# register.net
KiCad netlist of a schematic drawn in EAGLE
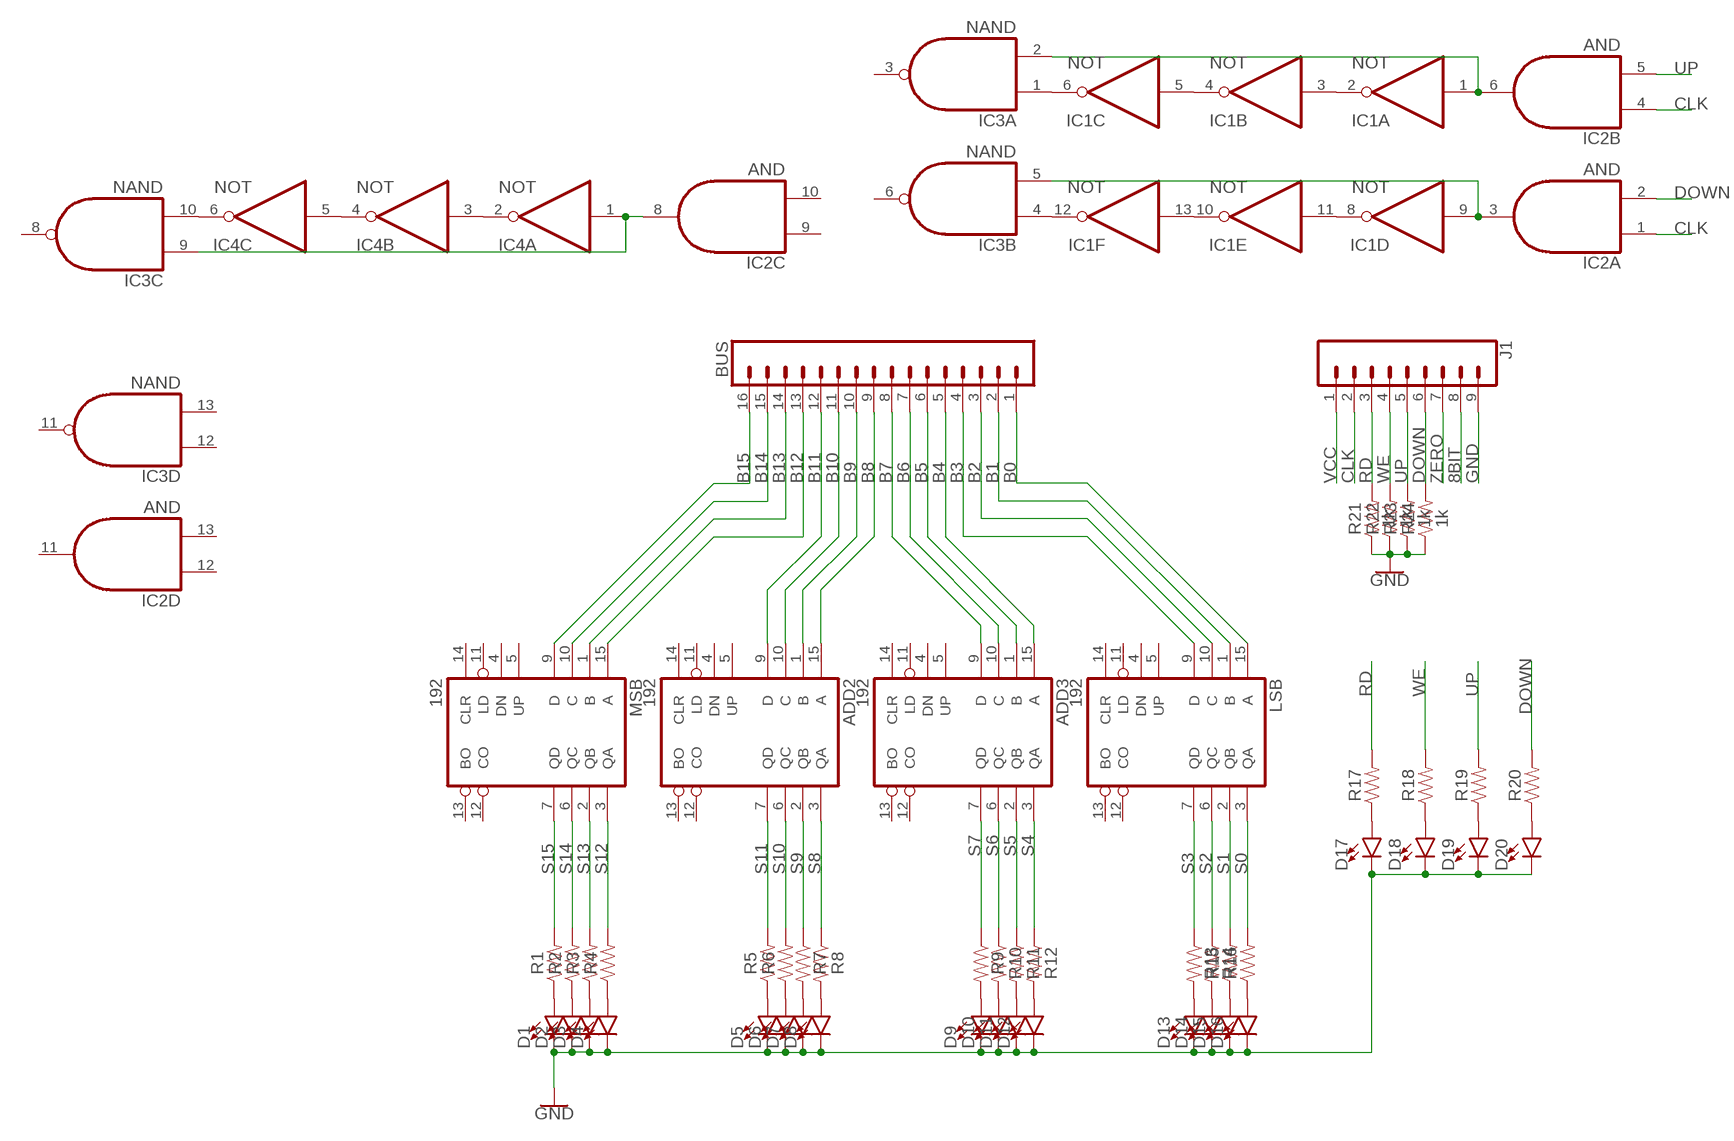
[diagram p0: schematic, sheet 1]

(export (version "E")
  (design (tool "Eeschema 10.0.6"))
  (components
    (comp (ref "ADD2")
      (value "192")
      (footprint "eagle-import:DIL16")
      (libsource (lib "eagle-import") (part "74192NLS"))
    )
    (comp (ref "ADD3")
      (value "192")
      (footprint "eagle-import:DIL16")
      (libsource (lib "eagle-import") (part "74192NLS"))
    )
    (comp (ref "BUS")
      (value "CONN_16")
      (footprint "eagle-import:1X16")
      (libsource (lib "eagle-import") (part "CONN_16"))
    )
    (comp (ref "D1")
      (value "LED5MM")
      (footprint "eagle-import:LED_5MM")
      (libsource (lib "eagle-import") (part "LED5MM"))
    )
    (comp (ref "D2")
      (value "LED5MM")
      (footprint "eagle-import:LED_5MM")
      (libsource (lib "eagle-import") (part "LED5MM"))
    )
    (comp (ref "D3")
      (value "LED5MM")
      (footprint "eagle-import:LED_5MM")
      (libsource (lib "eagle-import") (part "LED5MM"))
    )
    (comp (ref "D4")
      (value "LED5MM")
      (footprint "eagle-import:LED_5MM")
      (libsource (lib "eagle-import") (part "LED5MM"))
    )
    (comp (ref "D5")
      (value "LED5MM")
      (footprint "eagle-import:LED_5MM")
      (libsource (lib "eagle-import") (part "LED5MM"))
    )
    (comp (ref "D6")
      (value "LED5MM")
      (footprint "eagle-import:LED_5MM")
      (libsource (lib "eagle-import") (part "LED5MM"))
    )
    (comp (ref "D7")
      (value "LED5MM")
      (footprint "eagle-import:LED_5MM")
      (libsource (lib "eagle-import") (part "LED5MM"))
    )
    (comp (ref "D8")
      (value "LED5MM")
      (footprint "eagle-import:LED_5MM")
      (libsource (lib "eagle-import") (part "LED5MM"))
    )
    (comp (ref "D9")
      (value "LED5MM")
      (footprint "eagle-import:LED_5MM")
      (libsource (lib "eagle-import") (part "LED5MM"))
    )
    (comp (ref "D10")
      (value "LED5MM")
      (footprint "eagle-import:LED_5MM")
      (libsource (lib "eagle-import") (part "LED5MM"))
    )
    (comp (ref "D11")
      (value "LED5MM")
      (footprint "eagle-import:LED_5MM")
      (libsource (lib "eagle-import") (part "LED5MM"))
    )
    (comp (ref "D12")
      (value "LED5MM")
      (footprint "eagle-import:LED_5MM")
      (libsource (lib "eagle-import") (part "LED5MM"))
    )
    (comp (ref "D13")
      (value "LED5MM")
      (footprint "eagle-import:LED_5MM")
      (libsource (lib "eagle-import") (part "LED5MM"))
    )
    (comp (ref "D14")
      (value "LED5MM")
      (footprint "eagle-import:LED_5MM")
      (libsource (lib "eagle-import") (part "LED5MM"))
    )
    (comp (ref "D15")
      (value "LED5MM")
      (footprint "eagle-import:LED_5MM")
      (libsource (lib "eagle-import") (part "LED5MM"))
    )
    (comp (ref "D16")
      (value "LED5MM")
      (footprint "eagle-import:LED_5MM")
      (libsource (lib "eagle-import") (part "LED5MM"))
    )
    (comp (ref "D17")
      (value "LED5MM")
      (footprint "eagle-import:LED_5MM")
      (libsource (lib "eagle-import") (part "LED5MM"))
    )
    (comp (ref "D18")
      (value "LED5MM")
      (footprint "eagle-import:LED_5MM")
      (libsource (lib "eagle-import") (part "LED5MM"))
    )
    (comp (ref "D19")
      (value "LED5MM")
      (footprint "eagle-import:LED_5MM")
      (libsource (lib "eagle-import") (part "LED5MM"))
    )
    (comp (ref "D20")
      (value "LED5MM")
      (footprint "eagle-import:LED_5MM")
      (libsource (lib "eagle-import") (part "LED5MM"))
    )
    (comp (ref "IC1")
      (value "NOT")
      (footprint "eagle-import:DIL14")
      (libsource (lib "eagle-import") (part "7404NALS"))
    )
    (comp (ref "IC2")
      (value "AND")
      (footprint "eagle-import:DIL14")
      (libsource (lib "eagle-import") (part "7408NALS"))
    )
    (comp (ref "IC3")
      (value "NAND")
      (footprint "eagle-import:DIL14")
      (libsource (lib "eagle-import") (part "7400NALS"))
    )
    (comp (ref "IC4")
      (value "NOT")
      (footprint "eagle-import:DIL14")
      (libsource (lib "eagle-import") (part "7404NALS"))
    )
    (comp (ref "J1")
      (value "CONN_09")
      (footprint "eagle-import:1X09")
      (libsource (lib "eagle-import") (part "CONN_09"))
    )
    (comp (ref "LSB")
      (value "192")
      (footprint "eagle-import:DIL16")
      (libsource (lib "eagle-import") (part "74192NLS"))
    )
    (comp (ref "MSB")
      (value "192")
      (footprint "eagle-import:DIL16")
      (libsource (lib "eagle-import") (part "74192NLS"))
    )
    (comp (ref "R1")
      (value "RESISTORAXIAL-0.3")
      (footprint "eagle-import:AXIAL-0.3")
      (libsource (lib "eagle-import") (part "RESISTORAXIAL-0.3"))
    )
    (comp (ref "R2")
      (value "RESISTORAXIAL-0.3")
      (footprint "eagle-import:AXIAL-0.3")
      (libsource (lib "eagle-import") (part "RESISTORAXIAL-0.3"))
    )
    (comp (ref "R3")
      (value "RESISTORAXIAL-0.3")
      (footprint "eagle-import:AXIAL-0.3")
      (libsource (lib "eagle-import") (part "RESISTORAXIAL-0.3"))
    )
    (comp (ref "R4")
      (value "RESISTORAXIAL-0.3")
      (footprint "eagle-import:AXIAL-0.3")
      (libsource (lib "eagle-import") (part "RESISTORAXIAL-0.3"))
    )
    (comp (ref "R5")
      (value "RESISTORAXIAL-0.3")
      (footprint "eagle-import:AXIAL-0.3")
      (libsource (lib "eagle-import") (part "RESISTORAXIAL-0.3"))
    )
    (comp (ref "R6")
      (value "RESISTORAXIAL-0.3")
      (footprint "eagle-import:AXIAL-0.3")
      (libsource (lib "eagle-import") (part "RESISTORAXIAL-0.3"))
    )
    (comp (ref "R7")
      (value "RESISTORAXIAL-0.3")
      (footprint "eagle-import:AXIAL-0.3")
      (libsource (lib "eagle-import") (part "RESISTORAXIAL-0.3"))
    )
    (comp (ref "R8")
      (value "RESISTORAXIAL-0.3")
      (footprint "eagle-import:AXIAL-0.3")
      (libsource (lib "eagle-import") (part "RESISTORAXIAL-0.3"))
    )
    (comp (ref "R9")
      (value "RESISTORAXIAL-0.3")
      (footprint "eagle-import:AXIAL-0.3")
      (libsource (lib "eagle-import") (part "RESISTORAXIAL-0.3"))
    )
    (comp (ref "R10")
      (value "RESISTORAXIAL-0.3")
      (footprint "eagle-import:AXIAL-0.3")
      (libsource (lib "eagle-import") (part "RESISTORAXIAL-0.3"))
    )
    (comp (ref "R11")
      (value "RESISTORAXIAL-0.3")
      (footprint "eagle-import:AXIAL-0.3")
      (libsource (lib "eagle-import") (part "RESISTORAXIAL-0.3"))
    )
    (comp (ref "R12")
      (value "RESISTORAXIAL-0.3")
      (footprint "eagle-import:AXIAL-0.3")
      (libsource (lib "eagle-import") (part "RESISTORAXIAL-0.3"))
    )
    (comp (ref "R13")
      (value "RESISTORAXIAL-0.3")
      (footprint "eagle-import:AXIAL-0.3")
      (libsource (lib "eagle-import") (part "RESISTORAXIAL-0.3"))
    )
    (comp (ref "R14")
      (value "RESISTORAXIAL-0.3")
      (footprint "eagle-import:AXIAL-0.3")
      (libsource (lib "eagle-import") (part "RESISTORAXIAL-0.3"))
    )
    (comp (ref "R15")
      (value "RESISTORAXIAL-0.3")
      (footprint "eagle-import:AXIAL-0.3")
      (libsource (lib "eagle-import") (part "RESISTORAXIAL-0.3"))
    )
    (comp (ref "R16")
      (value "RESISTORAXIAL-0.3")
      (footprint "eagle-import:AXIAL-0.3")
      (libsource (lib "eagle-import") (part "RESISTORAXIAL-0.3"))
    )
    (comp (ref "R17")
      (value "RESISTORAXIAL-0.3")
      (footprint "eagle-import:AXIAL-0.3")
      (libsource (lib "eagle-import") (part "RESISTORAXIAL-0.3"))
    )
    (comp (ref "R18")
      (value "RESISTORAXIAL-0.3")
      (footprint "eagle-import:AXIAL-0.3")
      (libsource (lib "eagle-import") (part "RESISTORAXIAL-0.3"))
    )
    (comp (ref "R19")
      (value "RESISTORAXIAL-0.3")
      (footprint "eagle-import:AXIAL-0.3")
      (libsource (lib "eagle-import") (part "RESISTORAXIAL-0.3"))
    )
    (comp (ref "R20")
      (value "RESISTORAXIAL-0.3")
      (footprint "eagle-import:AXIAL-0.3")
      (libsource (lib "eagle-import") (part "RESISTORAXIAL-0.3"))
    )
    (comp (ref "R21")
      (value "1k")
      (footprint "eagle-import:AXIAL-0.3")
      (libsource (lib "eagle-import") (part "RESISTORAXIAL-0.3"))
    )
    (comp (ref "R22")
      (value "1k")
      (footprint "eagle-import:AXIAL-0.3")
      (libsource (lib "eagle-import") (part "RESISTORAXIAL-0.3"))
    )
    (comp (ref "R23")
      (value "1k")
      (footprint "eagle-import:AXIAL-0.3")
      (libsource (lib "eagle-import") (part "RESISTORAXIAL-0.3"))
    )
    (comp (ref "R24")
      (value "1k")
      (footprint "eagle-import:AXIAL-0.3")
      (libsource (lib "eagle-import") (part "RESISTORAXIAL-0.3"))
    )
  )
  (nets
    (net (code "1") (name "/8BIT") (class "Default")
      (node (ref "J1") (pin "8") (pinfunction "8_8") (pintype "passive"))
    )
    (net (code "2") (name "/B0") (class "Default")
      (node (ref "BUS") (pin "1") (pinfunction "1_1") (pintype "passive"))
      (node (ref "LSB") (pin "15") (pinfunction "A_15") (pintype "input"))
    )
    (net (code "3") (name "/B1") (class "Default")
      (node (ref "BUS") (pin "2") (pinfunction "2_2") (pintype "passive"))
      (node (ref "LSB") (pin "1") (pinfunction "B_1") (pintype "input"))
    )
    (net (code "4") (name "/B2") (class "Default")
      (node (ref "BUS") (pin "3") (pinfunction "3_3") (pintype "passive"))
      (node (ref "LSB") (pin "10") (pinfunction "C_10") (pintype "input"))
    )
    (net (code "5") (name "/B3") (class "Default")
      (node (ref "BUS") (pin "4") (pinfunction "4_4") (pintype "passive"))
      (node (ref "LSB") (pin "9") (pinfunction "D_9") (pintype "input"))
    )
    (net (code "6") (name "/B4") (class "Default")
      (node (ref "ADD3") (pin "15") (pinfunction "A_15") (pintype "input"))
      (node (ref "BUS") (pin "5") (pinfunction "5_5") (pintype "passive"))
    )
    (net (code "7") (name "/B5") (class "Default")
      (node (ref "ADD3") (pin "1") (pinfunction "B_1") (pintype "input"))
      (node (ref "BUS") (pin "6") (pinfunction "6_6") (pintype "passive"))
    )
    (net (code "8") (name "/B6") (class "Default")
      (node (ref "ADD3") (pin "10") (pinfunction "C_10") (pintype "input"))
      (node (ref "BUS") (pin "7") (pinfunction "7_7") (pintype "passive"))
    )
    (net (code "9") (name "/B7") (class "Default")
      (node (ref "ADD3") (pin "9") (pinfunction "D_9") (pintype "input"))
      (node (ref "BUS") (pin "8") (pinfunction "8_8") (pintype "passive"))
    )
    (net (code "10") (name "/B8") (class "Default")
      (node (ref "ADD2") (pin "15") (pinfunction "A_15") (pintype "input"))
      (node (ref "BUS") (pin "9") (pinfunction "9_9") (pintype "passive"))
    )
    (net (code "11") (name "/B9") (class "Default")
      (node (ref "ADD2") (pin "1") (pinfunction "B_1") (pintype "input"))
      (node (ref "BUS") (pin "10") (pinfunction "10_10") (pintype "passive"))
    )
    (net (code "12") (name "/B10") (class "Default")
      (node (ref "ADD2") (pin "10") (pinfunction "C_10") (pintype "input"))
      (node (ref "BUS") (pin "11") (pinfunction "11_11") (pintype "passive"))
    )
    (net (code "13") (name "/B11") (class "Default")
      (node (ref "ADD2") (pin "9") (pinfunction "D_9") (pintype "input"))
      (node (ref "BUS") (pin "12") (pinfunction "12_12") (pintype "passive"))
    )
    (net (code "14") (name "/B12") (class "Default")
      (node (ref "BUS") (pin "13") (pinfunction "13_13") (pintype "passive"))
      (node (ref "MSB") (pin "15") (pinfunction "A_15") (pintype "input"))
    )
    (net (code "15") (name "/B13") (class "Default")
      (node (ref "BUS") (pin "14") (pinfunction "14_14") (pintype "passive"))
      (node (ref "MSB") (pin "1") (pinfunction "B_1") (pintype "input"))
    )
    (net (code "16") (name "/B14") (class "Default")
      (node (ref "BUS") (pin "15") (pinfunction "15_15") (pintype "passive"))
      (node (ref "MSB") (pin "10") (pinfunction "C_10") (pintype "input"))
    )
    (net (code "17") (name "/B15") (class "Default")
      (node (ref "BUS") (pin "16") (pinfunction "16_16") (pintype "passive"))
      (node (ref "MSB") (pin "9") (pinfunction "D_9") (pintype "input"))
    )
    (net (code "18") (name "/CLK") (class "Default")
      (node (ref "IC2") (pin "1") (pinfunction "I0_1") (pintype "input"))
      (node (ref "IC2") (pin "4") (pinfunction "I0_4") (pintype "input"))
      (node (ref "J1") (pin "2") (pinfunction "2_2") (pintype "passive"))
    )
    (net (code "19") (name "/DOWN") (class "Default")
      (node (ref "IC2") (pin "2") (pinfunction "I1_2") (pintype "input"))
      (node (ref "J1") (pin "6") (pinfunction "6_6") (pintype "passive"))
      (node (ref "R20") (pin "P$2") (pinfunction "2_P$2") (pintype "passive"))
      (node (ref "R24") (pin "P$2") (pinfunction "2_P$2") (pintype "passive"))
    )
    (net (code "20") (name "/RD") (class "Default")
      (node (ref "J1") (pin "3") (pinfunction "3_3") (pintype "passive"))
      (node (ref "R17") (pin "P$2") (pinfunction "2_P$2") (pintype "passive"))
      (node (ref "R21") (pin "P$2") (pinfunction "2_P$2") (pintype "passive"))
    )
    (net (code "21") (name "/S0") (class "Default")
      (node (ref "LSB") (pin "3") (pinfunction "QA_3") (pintype "output"))
      (node (ref "R16") (pin "P$2") (pinfunction "2_P$2") (pintype "passive"))
    )
    (net (code "22") (name "/S1") (class "Default")
      (node (ref "LSB") (pin "2") (pinfunction "QB_2") (pintype "output"))
      (node (ref "R15") (pin "P$2") (pinfunction "2_P$2") (pintype "passive"))
    )
    (net (code "23") (name "/S2") (class "Default")
      (node (ref "LSB") (pin "6") (pinfunction "QC_6") (pintype "output"))
      (node (ref "R14") (pin "P$1") (pinfunction "1_P$1") (pintype "passive"))
    )
    (net (code "24") (name "/S3") (class "Default")
      (node (ref "LSB") (pin "7") (pinfunction "QD_7") (pintype "output"))
      (node (ref "R13") (pin "P$1") (pinfunction "1_P$1") (pintype "passive"))
    )
    (net (code "25") (name "/S4") (class "Default")
      (node (ref "ADD3") (pin "3") (pinfunction "QA_3") (pintype "output"))
      (node (ref "R12") (pin "P$1") (pinfunction "1_P$1") (pintype "passive"))
    )
    (net (code "26") (name "/S5") (class "Default")
      (node (ref "ADD3") (pin "2") (pinfunction "QB_2") (pintype "output"))
      (node (ref "R11") (pin "P$1") (pinfunction "1_P$1") (pintype "passive"))
    )
    (net (code "27") (name "/S6") (class "Default")
      (node (ref "ADD3") (pin "6") (pinfunction "QC_6") (pintype "output"))
      (node (ref "R10") (pin "P$1") (pinfunction "1_P$1") (pintype "passive"))
    )
    (net (code "28") (name "/S7") (class "Default")
      (node (ref "ADD3") (pin "7") (pinfunction "QD_7") (pintype "output"))
      (node (ref "R9") (pin "P$1") (pinfunction "1_P$1") (pintype "passive"))
    )
    (net (code "29") (name "/S8") (class "Default")
      (node (ref "ADD2") (pin "3") (pinfunction "QA_3") (pintype "output"))
      (node (ref "R8") (pin "P$1") (pinfunction "1_P$1") (pintype "passive"))
    )
    (net (code "30") (name "/S9") (class "Default")
      (node (ref "ADD2") (pin "2") (pinfunction "QB_2") (pintype "output"))
      (node (ref "R7") (pin "P$1") (pinfunction "1_P$1") (pintype "passive"))
    )
    (net (code "31") (name "/S10") (class "Default")
      (node (ref "ADD2") (pin "6") (pinfunction "QC_6") (pintype "output"))
      (node (ref "R6") (pin "P$2") (pinfunction "2_P$2") (pintype "passive"))
    )
    (net (code "32") (name "/S11") (class "Default")
      (node (ref "ADD2") (pin "7") (pinfunction "QD_7") (pintype "output"))
      (node (ref "R5") (pin "P$2") (pinfunction "2_P$2") (pintype "passive"))
    )
    (net (code "33") (name "/S12") (class "Default")
      (node (ref "MSB") (pin "3") (pinfunction "QA_3") (pintype "output"))
      (node (ref "R4") (pin "P$2") (pinfunction "2_P$2") (pintype "passive"))
    )
    (net (code "34") (name "/S13") (class "Default")
      (node (ref "MSB") (pin "2") (pinfunction "QB_2") (pintype "output"))
      (node (ref "R3") (pin "P$2") (pinfunction "2_P$2") (pintype "passive"))
    )
    (net (code "35") (name "/S14") (class "Default")
      (node (ref "MSB") (pin "6") (pinfunction "QC_6") (pintype "output"))
      (node (ref "R2") (pin "P$2") (pinfunction "2_P$2") (pintype "passive"))
    )
    (net (code "36") (name "/S15") (class "Default")
      (node (ref "MSB") (pin "7") (pinfunction "QD_7") (pintype "output"))
      (node (ref "R1") (pin "P$2") (pinfunction "2_P$2") (pintype "passive"))
    )
    (net (code "37") (name "/UP") (class "Default")
      (node (ref "IC2") (pin "5") (pinfunction "I1_5") (pintype "input"))
      (node (ref "J1") (pin "5") (pinfunction "5_5") (pintype "passive"))
      (node (ref "R19") (pin "P$2") (pinfunction "2_P$2") (pintype "passive"))
      (node (ref "R23") (pin "P$2") (pinfunction "2_P$2") (pintype "passive"))
    )
    (net (code "38") (name "/VCC") (class "Default")
      (node (ref "J1") (pin "1") (pinfunction "1_1") (pintype "passive"))
    )
    (net (code "39") (name "/WE") (class "Default")
      (node (ref "J1") (pin "4") (pinfunction "4_4") (pintype "passive"))
      (node (ref "R18") (pin "P$2") (pinfunction "2_P$2") (pintype "passive"))
      (node (ref "R22") (pin "P$2") (pinfunction "2_P$2") (pintype "passive"))
    )
    (net (code "40") (name "/ZERO") (class "Default")
      (node (ref "J1") (pin "7") (pinfunction "7_7") (pintype "passive"))
    )
    (net (code "41") (name "GND") (class "Default")
      (node (ref "D1") (pin "K") (pinfunction "C_K") (pintype "passive"))
      (node (ref "D10") (pin "K") (pinfunction "C_K") (pintype "passive"))
      (node (ref "D11") (pin "K") (pinfunction "C_K") (pintype "passive"))
      (node (ref "D12") (pin "K") (pinfunction "C_K") (pintype "passive"))
      (node (ref "D13") (pin "K") (pinfunction "C_K") (pintype "passive"))
      (node (ref "D14") (pin "K") (pinfunction "C_K") (pintype "passive"))
      (node (ref "D15") (pin "K") (pinfunction "C_K") (pintype "passive"))
      (node (ref "D16") (pin "K") (pinfunction "C_K") (pintype "passive"))
      (node (ref "D17") (pin "K") (pinfunction "C_K") (pintype "passive"))
      (node (ref "D18") (pin "K") (pinfunction "C_K") (pintype "passive"))
      (node (ref "D19") (pin "K") (pinfunction "C_K") (pintype "passive"))
      (node (ref "D2") (pin "K") (pinfunction "C_K") (pintype "passive"))
      (node (ref "D20") (pin "K") (pinfunction "C_K") (pintype "passive"))
      (node (ref "D3") (pin "K") (pinfunction "C_K") (pintype "passive"))
      (node (ref "D4") (pin "K") (pinfunction "C_K") (pintype "passive"))
      (node (ref "D5") (pin "K") (pinfunction "C_K") (pintype "passive"))
      (node (ref "D6") (pin "K") (pinfunction "C_K") (pintype "passive"))
      (node (ref "D7") (pin "K") (pinfunction "C_K") (pintype "passive"))
      (node (ref "D8") (pin "K") (pinfunction "C_K") (pintype "passive"))
      (node (ref "D9") (pin "K") (pinfunction "C_K") (pintype "passive"))
      (node (ref "J1") (pin "9") (pinfunction "9_9") (pintype "passive"))
      (node (ref "R21") (pin "P$1") (pinfunction "1_P$1") (pintype "passive"))
      (node (ref "R22") (pin "P$1") (pinfunction "1_P$1") (pintype "passive"))
      (node (ref "R23") (pin "P$1") (pinfunction "1_P$1") (pintype "passive"))
      (node (ref "R24") (pin "P$1") (pinfunction "1_P$1") (pintype "passive"))
    )
    (net (code "42") (name "Net-(IC1A-I)") (class "Default")
      (node (ref "IC1") (pin "1") (pinfunction "I_1") (pintype "input"))
      (node (ref "IC2") (pin "6") (pinfunction "O_6") (pintype "output"))
      (node (ref "IC3") (pin "2") (pinfunction "I1_2") (pintype "input"))
    )
    (net (code "43") (name "Net-(IC1A-O)") (class "Default")
      (node (ref "IC1") (pin "2") (pinfunction "O_2") (pintype "output"))
      (node (ref "IC1") (pin "3") (pinfunction "I_3") (pintype "input"))
    )
    (net (code "44") (name "Net-(IC1B-O)") (class "Default")
      (node (ref "IC1") (pin "4") (pinfunction "O_4") (pintype "output"))
      (node (ref "IC1") (pin "5") (pinfunction "I_5") (pintype "input"))
    )
    (net (code "45") (name "Net-(IC1C-O)") (class "Default")
      (node (ref "IC1") (pin "6") (pinfunction "O_6") (pintype "output"))
      (node (ref "IC3") (pin "1") (pinfunction "I0_1") (pintype "input"))
    )
    (net (code "46") (name "Net-(IC1D-I)") (class "Default")
      (node (ref "IC1") (pin "9") (pinfunction "I_9") (pintype "input"))
      (node (ref "IC2") (pin "3") (pinfunction "O_3") (pintype "output"))
      (node (ref "IC3") (pin "5") (pinfunction "I1_5") (pintype "input"))
    )
    (net (code "47") (name "Net-(IC1D-O)") (class "Default")
      (node (ref "IC1") (pin "11") (pinfunction "I_11") (pintype "input"))
      (node (ref "IC1") (pin "8") (pinfunction "O_8") (pintype "output"))
    )
    (net (code "48") (name "Net-(IC1E-O)") (class "Default")
      (node (ref "IC1") (pin "10") (pinfunction "O_10") (pintype "output"))
      (node (ref "IC1") (pin "13") (pinfunction "I_13") (pintype "input"))
    )
    (net (code "49") (name "Net-(IC1F-O)") (class "Default")
      (node (ref "IC1") (pin "12") (pinfunction "O_12") (pintype "output"))
      (node (ref "IC3") (pin "4") (pinfunction "I0_4") (pintype "input"))
    )
    (net (code "50") (name "Net-(IC2C-O)") (class "Default")
      (node (ref "IC2") (pin "8") (pinfunction "O_8") (pintype "output"))
      (node (ref "IC3") (pin "9") (pinfunction "I0_9") (pintype "input"))
      (node (ref "IC4") (pin "1") (pinfunction "I_1") (pintype "input"))
    )
    (net (code "51") (name "Net-(IC3C-I1)") (class "Default")
      (node (ref "IC3") (pin "10") (pinfunction "I1_10") (pintype "input"))
      (node (ref "IC4") (pin "6") (pinfunction "O_6") (pintype "output"))
    )
    (net (code "52") (name "Net-(IC4A-O)") (class "Default")
      (node (ref "IC4") (pin "2") (pinfunction "O_2") (pintype "output"))
      (node (ref "IC4") (pin "3") (pinfunction "I_3") (pintype "input"))
    )
    (net (code "53") (name "Net-(IC4B-O)") (class "Default")
      (node (ref "IC4") (pin "4") (pinfunction "O_4") (pintype "output"))
      (node (ref "IC4") (pin "5") (pinfunction "I_5") (pintype "input"))
    )
    (net (code "54") (name "Net-(R1-1)") (class "Default")
      (node (ref "D1") (pin "A") (pinfunction "A_A") (pintype "passive"))
      (node (ref "R1") (pin "P$1") (pinfunction "1_P$1") (pintype "passive"))
    )
    (net (code "55") (name "Net-(R2-1)") (class "Default")
      (node (ref "D2") (pin "A") (pinfunction "A_A") (pintype "passive"))
      (node (ref "R2") (pin "P$1") (pinfunction "1_P$1") (pintype "passive"))
    )
    (net (code "56") (name "Net-(R3-1)") (class "Default")
      (node (ref "D3") (pin "A") (pinfunction "A_A") (pintype "passive"))
      (node (ref "R3") (pin "P$1") (pinfunction "1_P$1") (pintype "passive"))
    )
    (net (code "57") (name "Net-(R4-1)") (class "Default")
      (node (ref "D4") (pin "A") (pinfunction "A_A") (pintype "passive"))
      (node (ref "R4") (pin "P$1") (pinfunction "1_P$1") (pintype "passive"))
    )
    (net (code "58") (name "Net-(R5-1)") (class "Default")
      (node (ref "D5") (pin "A") (pinfunction "A_A") (pintype "passive"))
      (node (ref "R5") (pin "P$1") (pinfunction "1_P$1") (pintype "passive"))
    )
    (net (code "59") (name "Net-(R6-1)") (class "Default")
      (node (ref "D6") (pin "A") (pinfunction "A_A") (pintype "passive"))
      (node (ref "R6") (pin "P$1") (pinfunction "1_P$1") (pintype "passive"))
    )
    (net (code "60") (name "Net-(R7-2)") (class "Default")
      (node (ref "D7") (pin "A") (pinfunction "A_A") (pintype "passive"))
      (node (ref "R7") (pin "P$2") (pinfunction "2_P$2") (pintype "passive"))
    )
    (net (code "61") (name "Net-(R8-2)") (class "Default")
      (node (ref "D8") (pin "A") (pinfunction "A_A") (pintype "passive"))
      (node (ref "R8") (pin "P$2") (pinfunction "2_P$2") (pintype "passive"))
    )
    (net (code "62") (name "Net-(R9-2)") (class "Default")
      (node (ref "D9") (pin "A") (pinfunction "A_A") (pintype "passive"))
      (node (ref "R9") (pin "P$2") (pinfunction "2_P$2") (pintype "passive"))
    )
    (net (code "63") (name "Net-(R10-2)") (class "Default")
      (node (ref "D10") (pin "A") (pinfunction "A_A") (pintype "passive"))
      (node (ref "R10") (pin "P$2") (pinfunction "2_P$2") (pintype "passive"))
    )
    (net (code "64") (name "Net-(R11-2)") (class "Default")
      (node (ref "D11") (pin "A") (pinfunction "A_A") (pintype "passive"))
      (node (ref "R11") (pin "P$2") (pinfunction "2_P$2") (pintype "passive"))
    )
    (net (code "65") (name "Net-(R12-2)") (class "Default")
      (node (ref "D12") (pin "A") (pinfunction "A_A") (pintype "passive"))
      (node (ref "R12") (pin "P$2") (pinfunction "2_P$2") (pintype "passive"))
    )
    (net (code "66") (name "Net-(R13-2)") (class "Default")
      (node (ref "D13") (pin "A") (pinfunction "A_A") (pintype "passive"))
      (node (ref "R13") (pin "P$2") (pinfunction "2_P$2") (pintype "passive"))
    )
    (net (code "67") (name "Net-(R14-2)") (class "Default")
      (node (ref "D14") (pin "A") (pinfunction "A_A") (pintype "passive"))
      (node (ref "R14") (pin "P$2") (pinfunction "2_P$2") (pintype "passive"))
    )
    (net (code "68") (name "Net-(R15-1)") (class "Default")
      (node (ref "D15") (pin "A") (pinfunction "A_A") (pintype "passive"))
      (node (ref "R15") (pin "P$1") (pinfunction "1_P$1") (pintype "passive"))
    )
    (net (code "69") (name "Net-(R16-1)") (class "Default")
      (node (ref "D16") (pin "A") (pinfunction "A_A") (pintype "passive"))
      (node (ref "R16") (pin "P$1") (pinfunction "1_P$1") (pintype "passive"))
    )
    (net (code "70") (name "Net-(R17-1)") (class "Default")
      (node (ref "D17") (pin "A") (pinfunction "A_A") (pintype "passive"))
      (node (ref "R17") (pin "P$1") (pinfunction "1_P$1") (pintype "passive"))
    )
    (net (code "71") (name "Net-(R18-1)") (class "Default")
      (node (ref "D18") (pin "A") (pinfunction "A_A") (pintype "passive"))
      (node (ref "R18") (pin "P$1") (pinfunction "1_P$1") (pintype "passive"))
    )
    (net (code "72") (name "Net-(R19-1)") (class "Default")
      (node (ref "D19") (pin "A") (pinfunction "A_A") (pintype "passive"))
      (node (ref "R19") (pin "P$1") (pinfunction "1_P$1") (pintype "passive"))
    )
    (net (code "73") (name "Net-(R20-1)") (class "Default")
      (node (ref "D20") (pin "A") (pinfunction "A_A") (pintype "passive"))
      (node (ref "R20") (pin "P$1") (pinfunction "1_P$1") (pintype "passive"))
    )
    (net (code "74") (name "unconnected-(ADD2A-BO-Pad13)") (class "Default")
      (node (ref "ADD2") (pin "13") (pinfunction "BO_13") (pintype "output"))
    )
    (net (code "75") (name "unconnected-(ADD2A-CLR-Pad14)") (class "Default")
      (node (ref "ADD2") (pin "14") (pinfunction "CLR_14") (pintype "input"))
    )
    (net (code "76") (name "unconnected-(ADD2A-CO-Pad12)") (class "Default")
      (node (ref "ADD2") (pin "12") (pinfunction "CO_12") (pintype "output"))
    )
    (net (code "77") (name "unconnected-(ADD2A-DN-Pad4)") (class "Default")
      (node (ref "ADD2") (pin "4") (pinfunction "DN_4") (pintype "input"))
    )
    (net (code "78") (name "unconnected-(ADD2A-LD-Pad11)") (class "Default")
      (node (ref "ADD2") (pin "11") (pinfunction "LD_11") (pintype "input"))
    )
    (net (code "79") (name "unconnected-(ADD2A-UP-Pad5)") (class "Default")
      (node (ref "ADD2") (pin "5") (pinfunction "UP_5") (pintype "input"))
    )
    (net (code "80") (name "unconnected-(ADD3A-BO-Pad13)") (class "Default")
      (node (ref "ADD3") (pin "13") (pinfunction "BO_13") (pintype "output"))
    )
    (net (code "81") (name "unconnected-(ADD3A-CLR-Pad14)") (class "Default")
      (node (ref "ADD3") (pin "14") (pinfunction "CLR_14") (pintype "input"))
    )
    (net (code "82") (name "unconnected-(ADD3A-CO-Pad12)") (class "Default")
      (node (ref "ADD3") (pin "12") (pinfunction "CO_12") (pintype "output"))
    )
    (net (code "83") (name "unconnected-(ADD3A-DN-Pad4)") (class "Default")
      (node (ref "ADD3") (pin "4") (pinfunction "DN_4") (pintype "input"))
    )
    (net (code "84") (name "unconnected-(ADD3A-LD-Pad11)") (class "Default")
      (node (ref "ADD3") (pin "11") (pinfunction "LD_11") (pintype "input"))
    )
    (net (code "85") (name "unconnected-(ADD3A-UP-Pad5)") (class "Default")
      (node (ref "ADD3") (pin "5") (pinfunction "UP_5") (pintype "input"))
    )
    (net (code "86") (name "unconnected-(IC2C-I0-Pad9)") (class "Default")
      (node (ref "IC2") (pin "9") (pinfunction "I0_9") (pintype "input"))
    )
    (net (code "87") (name "unconnected-(IC2C-I1-Pad10)") (class "Default")
      (node (ref "IC2") (pin "10") (pinfunction "I1_10") (pintype "input"))
    )
    (net (code "88") (name "unconnected-(IC2D-I0-Pad12)") (class "Default")
      (node (ref "IC2") (pin "12") (pinfunction "I0_12") (pintype "input"))
    )
    (net (code "89") (name "unconnected-(IC2D-I1-Pad13)") (class "Default")
      (node (ref "IC2") (pin "13") (pinfunction "I1_13") (pintype "input"))
    )
    (net (code "90") (name "unconnected-(IC2D-O-Pad11)") (class "Default")
      (node (ref "IC2") (pin "11") (pinfunction "O_11") (pintype "output"))
    )
    (net (code "91") (name "unconnected-(IC3A-O-Pad3)") (class "Default")
      (node (ref "IC3") (pin "3") (pinfunction "O_3") (pintype "output"))
    )
    (net (code "92") (name "unconnected-(IC3B-O-Pad6)") (class "Default")
      (node (ref "IC3") (pin "6") (pinfunction "O_6") (pintype "output"))
    )
    (net (code "93") (name "unconnected-(IC3C-O-Pad8)") (class "Default")
      (node (ref "IC3") (pin "8") (pinfunction "O_8") (pintype "output"))
    )
    (net (code "94") (name "unconnected-(IC3D-I0-Pad12)") (class "Default")
      (node (ref "IC3") (pin "12") (pinfunction "I0_12") (pintype "input"))
    )
    (net (code "95") (name "unconnected-(IC3D-I1-Pad13)") (class "Default")
      (node (ref "IC3") (pin "13") (pinfunction "I1_13") (pintype "input"))
    )
    (net (code "96") (name "unconnected-(IC3D-O-Pad11)") (class "Default")
      (node (ref "IC3") (pin "11") (pinfunction "O_11") (pintype "output"))
    )
    (net (code "97") (name "unconnected-(LSBA-BO-Pad13)") (class "Default")
      (node (ref "LSB") (pin "13") (pinfunction "BO_13") (pintype "output"))
    )
    (net (code "98") (name "unconnected-(LSBA-CLR-Pad14)") (class "Default")
      (node (ref "LSB") (pin "14") (pinfunction "CLR_14") (pintype "input"))
    )
    (net (code "99") (name "unconnected-(LSBA-CO-Pad12)") (class "Default")
      (node (ref "LSB") (pin "12") (pinfunction "CO_12") (pintype "output"))
    )
    (net (code "100") (name "unconnected-(LSBA-DN-Pad4)") (class "Default")
      (node (ref "LSB") (pin "4") (pinfunction "DN_4") (pintype "input"))
    )
    (net (code "101") (name "unconnected-(LSBA-LD-Pad11)") (class "Default")
      (node (ref "LSB") (pin "11") (pinfunction "LD_11") (pintype "input"))
    )
    (net (code "102") (name "unconnected-(LSBA-UP-Pad5)") (class "Default")
      (node (ref "LSB") (pin "5") (pinfunction "UP_5") (pintype "input"))
    )
    (net (code "103") (name "unconnected-(MSBA-BO-Pad13)") (class "Default")
      (node (ref "MSB") (pin "13") (pinfunction "BO_13") (pintype "output"))
    )
    (net (code "104") (name "unconnected-(MSBA-CLR-Pad14)") (class "Default")
      (node (ref "MSB") (pin "14") (pinfunction "CLR_14") (pintype "input"))
    )
    (net (code "105") (name "unconnected-(MSBA-CO-Pad12)") (class "Default")
      (node (ref "MSB") (pin "12") (pinfunction "CO_12") (pintype "output"))
    )
    (net (code "106") (name "unconnected-(MSBA-DN-Pad4)") (class "Default")
      (node (ref "MSB") (pin "4") (pinfunction "DN_4") (pintype "input"))
    )
    (net (code "107") (name "unconnected-(MSBA-LD-Pad11)") (class "Default")
      (node (ref "MSB") (pin "11") (pinfunction "LD_11") (pintype "input"))
    )
    (net (code "108") (name "unconnected-(MSBA-UP-Pad5)") (class "Default")
      (node (ref "MSB") (pin "5") (pinfunction "UP_5") (pintype "input"))
    )
  )
)
